# ir_remote_v2.net
KiCad netlist of a schematic drawn in EAGLE
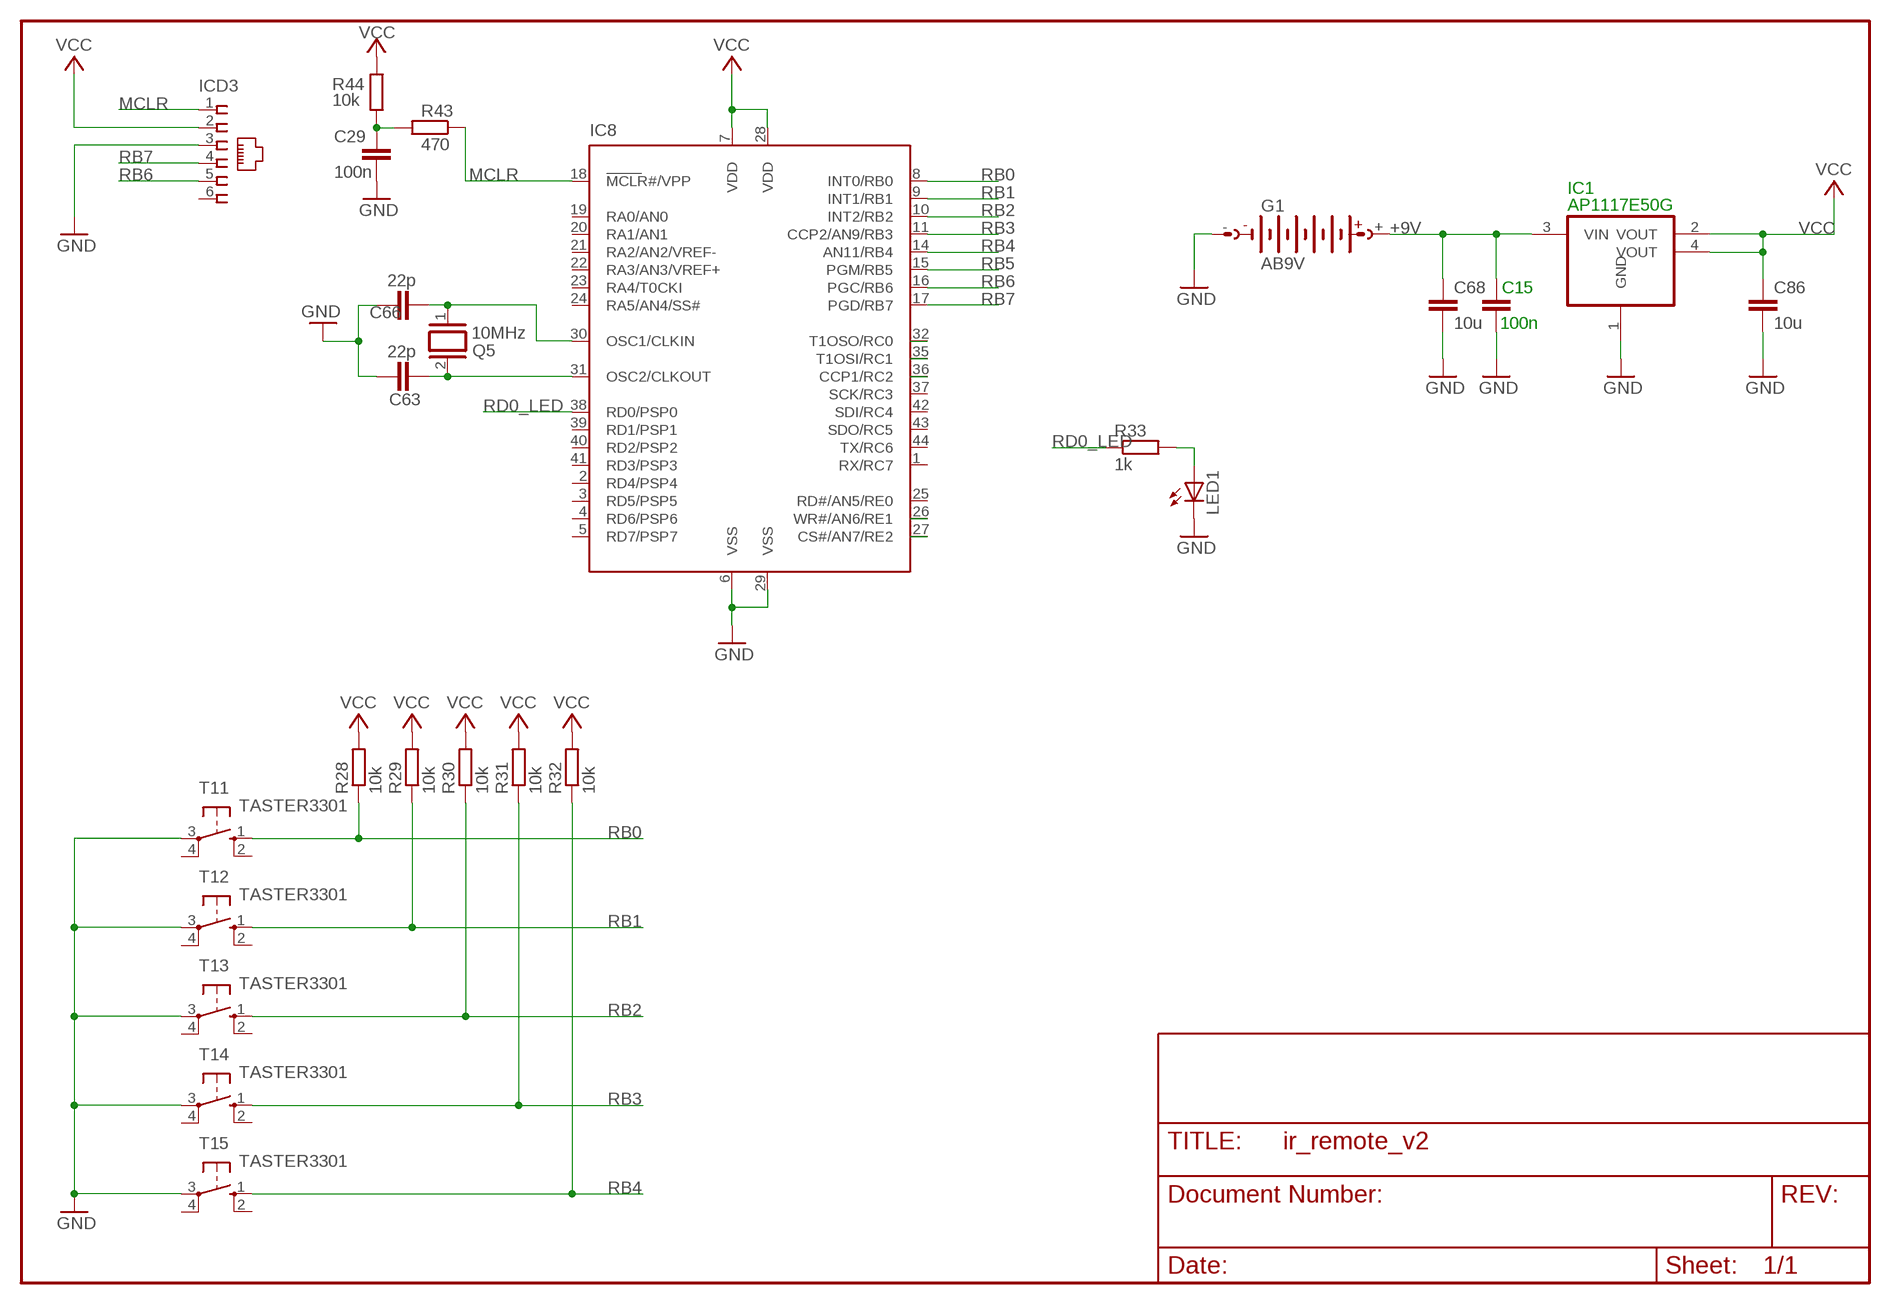
[diagram p0: schematic, sheet 1]

(export (version "E")
  (design (tool "Eeschema 10.0.6"))
  (components
    (comp (ref "C15")
      (value "100n")
      (footprint "eagle-import:C0805")
      (libsource (lib "eagle-import") (part "rcl_416_C-EUC0805"))
    )
    (comp (ref "C29")
      (value "100n")
      (footprint "eagle-import:C0805")
      (libsource (lib "eagle-import") (part "C-EUC0805"))
    )
    (comp (ref "C63")
      (value "22p")
      (footprint "eagle-import:C0603_WE")
      (libsource (lib "eagle-import") (part "C-EUC0603_WE"))
    )
    (comp (ref "C66")
      (value "22p")
      (footprint "eagle-import:C0603_WE")
      (libsource (lib "eagle-import") (part "C-EUC0603_WE"))
    )
    (comp (ref "C68")
      (value "10u")
      (footprint "eagle-import:C0805")
      (libsource (lib "eagle-import") (part "C-EUC0805"))
    )
    (comp (ref "C86")
      (value "10u")
      (footprint "eagle-import:C0805")
      (libsource (lib "eagle-import") (part "C-EUC0805"))
    )
    (comp (ref "G1")
      (value "AB9V")
      (footprint "eagle-import:AB9V")
      (libsource (lib "eagle-import") (part "AB9V"))
    )
    (comp (ref "IC1")
      (value "AP1117E50G")
      (footprint "eagle-import:SOT223")
      (libsource (lib "eagle-import") (part "REG1117-2OUT"))
    )
    (comp (ref "IC8")
      (value "PIC18F4520")
      (footprint "eagle-import:TQFP44")
      (libsource (lib "eagle-import") (part "PIC18F4520"))
    )
    (comp (ref "ICD3")
      (value "520250-3")
      (footprint "eagle-import:520250-3")
      (libsource (lib "eagle-import") (part "520250-3"))
    )
    (comp (ref "LED1")
      (value "LED5MM")
      (footprint "eagle-import:LED5MM")
      (libsource (lib "eagle-import") (part "LED5MM"))
    )
    (comp (ref "Q5")
      (value "10MHz")
      (footprint "eagle-import:QUARZ_HC5032_2")
      (libsource (lib "eagle-import") (part "XTAL_HC5032"))
    )
    (comp (ref "R28")
      (value "10k")
      (footprint "eagle-import:0207_7")
      (libsource (lib "eagle-import") (part "R-EU_0207/7"))
    )
    (comp (ref "R29")
      (value "10k")
      (footprint "eagle-import:0207_7")
      (libsource (lib "eagle-import") (part "R-EU_0207/7"))
    )
    (comp (ref "R30")
      (value "10k")
      (footprint "eagle-import:0207_7")
      (libsource (lib "eagle-import") (part "R-EU_0207/7"))
    )
    (comp (ref "R31")
      (value "10k")
      (footprint "eagle-import:0207_7")
      (libsource (lib "eagle-import") (part "R-EU_0207/7"))
    )
    (comp (ref "R32")
      (value "10k")
      (footprint "eagle-import:0207_7")
      (libsource (lib "eagle-import") (part "R-EU_0207/7"))
    )
    (comp (ref "R33")
      (value "1k")
      (footprint "eagle-import:0207_10")
      (libsource (lib "eagle-import") (part "resistor_R-EU_0207/10"))
    )
    (comp (ref "R43")
      (value "470")
      (footprint "eagle-import:M0805")
      (libsource (lib "eagle-import") (part "R-EU_M0805"))
    )
    (comp (ref "R44")
      (value "10k")
      (footprint "eagle-import:M0805")
      (libsource (lib "eagle-import") (part "R-EU_M0805"))
    )
    (comp (ref "T11")
      (value "TASTER3301")
      (footprint "eagle-import:TASTER3301")
      (libsource (lib "eagle-import") (part "TASTER3301"))
    )
    (comp (ref "T12")
      (value "TASTER3301")
      (footprint "eagle-import:TASTER3301")
      (libsource (lib "eagle-import") (part "TASTER3301"))
    )
    (comp (ref "T13")
      (value "TASTER3301")
      (footprint "eagle-import:TASTER3301")
      (libsource (lib "eagle-import") (part "TASTER3301"))
    )
    (comp (ref "T14")
      (value "TASTER3301")
      (footprint "eagle-import:TASTER3301")
      (libsource (lib "eagle-import") (part "TASTER3301"))
    )
    (comp (ref "T15")
      (value "TASTER3301")
      (footprint "eagle-import:TASTER3301")
      (libsource (lib "eagle-import") (part "TASTER3301"))
    )
  )
  (nets
    (net (code "1") (name "/+9V") (class "Default")
      (node (ref "C15") (pin "1") (pinfunction "1_1") (pintype "passive"))
      (node (ref "C68") (pin "1") (pinfunction "1_1") (pintype "passive"))
      (node (ref "G1") (pin "+") (pinfunction "+_+") (pintype "passive"))
      (node (ref "IC1") (pin "3") (pinfunction "VIN_3") (pintype "input"))
    )
    (net (code "2") (name "/MCLR") (class "Default")
      (node (ref "IC8") (pin "18") (pinfunction "MCLR#/VPP_18") (pintype "input"))
      (node (ref "ICD3") (pin "1") (pinfunction "1_1") (pintype "passive"))
      (node (ref "R43") (pin "1") (pinfunction "1_1") (pintype "passive"))
    )
    (net (code "3") (name "/RB0") (class "Default")
      (node (ref "IC8") (pin "8") (pinfunction "INT0/RB0_8") (pintype "bidirectional"))
      (node (ref "R28") (pin "1") (pinfunction "1_1") (pintype "passive"))
      (node (ref "T11") (pin "1") (pinfunction "S_1") (pintype "passive"))
    )
    (net (code "4") (name "/RB1") (class "Default")
      (node (ref "IC8") (pin "35") (pinfunction "T1OSI/RC1_35") (pintype "bidirectional"))
      (node (ref "IC8") (pin "9") (pinfunction "INT1/RB1_9") (pintype "bidirectional"))
      (node (ref "R29") (pin "1") (pinfunction "1_1") (pintype "passive"))
      (node (ref "T12") (pin "1") (pinfunction "S_1") (pintype "passive"))
    )
    (net (code "5") (name "/RB2") (class "Default")
      (node (ref "IC8") (pin "10") (pinfunction "INT2/RB2_10") (pintype "bidirectional"))
      (node (ref "IC8") (pin "32") (pinfunction "T1OSO/RC0_32") (pintype "bidirectional"))
      (node (ref "R30") (pin "1") (pinfunction "1_1") (pintype "passive"))
      (node (ref "T13") (pin "1") (pinfunction "S_1") (pintype "passive"))
    )
    (net (code "6") (name "/RB3") (class "Default")
      (node (ref "IC8") (pin "11") (pinfunction "CCP2/AN9/RB3_11") (pintype "bidirectional"))
      (node (ref "R31") (pin "1") (pinfunction "1_1") (pintype "passive"))
      (node (ref "T14") (pin "1") (pinfunction "S_1") (pintype "passive"))
    )
    (net (code "7") (name "/RB4") (class "Default")
      (node (ref "IC8") (pin "14") (pinfunction "AN11/RB4_14") (pintype "bidirectional"))
      (node (ref "R32") (pin "1") (pinfunction "1_1") (pintype "passive"))
      (node (ref "T15") (pin "1") (pinfunction "S_1") (pintype "passive"))
    )
    (net (code "8") (name "/RB5") (class "Default")
      (node (ref "IC8") (pin "15") (pinfunction "PGM/RB5_15") (pintype "bidirectional"))
    )
    (net (code "9") (name "/RB6") (class "Default")
      (node (ref "IC8") (pin "16") (pinfunction "PGC/RB6_16") (pintype "bidirectional"))
      (node (ref "ICD3") (pin "5") (pinfunction "5_5") (pintype "passive"))
    )
    (net (code "10") (name "/RB7") (class "Default")
      (node (ref "IC8") (pin "17") (pinfunction "PGD/RB7_17") (pintype "bidirectional"))
      (node (ref "ICD3") (pin "4") (pinfunction "4_4") (pintype "passive"))
    )
    (net (code "11") (name "/RD0_LED") (class "Default")
      (node (ref "IC8") (pin "38") (pinfunction "RD0/PSP0_38") (pintype "bidirectional"))
      (node (ref "R33") (pin "1") (pinfunction "1_1") (pintype "passive"))
    )
    (net (code "12") (name "GND") (class "Default")
      (node (ref "C15") (pin "2") (pinfunction "2_2") (pintype "passive"))
      (node (ref "C29") (pin "2") (pinfunction "2_2") (pintype "passive"))
      (node (ref "C63") (pin "1") (pinfunction "1_1") (pintype "passive"))
      (node (ref "C66") (pin "1") (pinfunction "1_1") (pintype "passive"))
      (node (ref "C68") (pin "2") (pinfunction "2_2") (pintype "passive"))
      (node (ref "C86") (pin "2") (pinfunction "2_2") (pintype "passive"))
      (node (ref "G1") (pin "-") (pinfunction "-_-") (pintype "passive"))
      (node (ref "IC1") (pin "1") (pinfunction "GND_1") (pintype "power_in"))
      (node (ref "IC8") (pin "29") (pinfunction "VSS_29") (pintype "bidirectional"))
      (node (ref "IC8") (pin "6") (pinfunction "VSS_6") (pintype "bidirectional"))
      (node (ref "ICD3") (pin "3") (pinfunction "3_3") (pintype "passive"))
      (node (ref "LED1") (pin "K") (pinfunction "C_K") (pintype "passive"))
      (node (ref "T11") (pin "3") (pinfunction "P_3") (pintype "passive"))
      (node (ref "T12") (pin "3") (pinfunction "P_3") (pintype "passive"))
      (node (ref "T13") (pin "3") (pinfunction "P_3") (pintype "passive"))
      (node (ref "T14") (pin "3") (pinfunction "P_3") (pintype "passive"))
      (node (ref "T15") (pin "3") (pinfunction "P_3") (pintype "passive"))
    )
    (net (code "13") (name "Net-(C29-Pad1)") (class "Default")
      (node (ref "C29") (pin "1") (pinfunction "1_1") (pintype "passive"))
      (node (ref "R43") (pin "2") (pinfunction "2_2") (pintype "passive"))
      (node (ref "R44") (pin "2") (pinfunction "2_2") (pintype "passive"))
    )
    (net (code "14") (name "Net-(IC8-OSC1{slash}CLKIN)") (class "Default")
      (node (ref "C66") (pin "2") (pinfunction "2_2") (pintype "passive"))
      (node (ref "IC8") (pin "30") (pinfunction "OSC1/CLKIN_30") (pintype "input"))
      (node (ref "Q5") (pin "1") (pinfunction "1_1") (pintype "passive"))
    )
    (net (code "15") (name "Net-(IC8-OSC2{slash}CLKOUT)") (class "Default")
      (node (ref "C63") (pin "2") (pinfunction "2_2") (pintype "passive"))
      (node (ref "IC8") (pin "31") (pinfunction "OSC2/CLKOUT_31") (pintype "output"))
      (node (ref "Q5") (pin "2") (pinfunction "2_2") (pintype "passive"))
    )
    (net (code "16") (name "Net-(LED1-PadA)") (class "Default")
      (node (ref "LED1") (pin "A") (pinfunction "A_A") (pintype "passive"))
      (node (ref "R33") (pin "2") (pinfunction "2_2") (pintype "passive"))
    )
    (net (code "17") (name "VCC") (class "Default")
      (node (ref "C86") (pin "1") (pinfunction "1_1") (pintype "passive"))
      (node (ref "IC1") (pin "2") (pinfunction "VOUT_2") (pintype "output"))
      (node (ref "IC1") (pin "4") (pinfunction "VOUT_4") (pintype "bidirectional"))
      (node (ref "IC8") (pin "28") (pinfunction "VDD_28") (pintype "bidirectional"))
      (node (ref "IC8") (pin "7") (pinfunction "VDD_7") (pintype "bidirectional"))
      (node (ref "ICD3") (pin "2") (pinfunction "2_2") (pintype "passive"))
      (node (ref "R28") (pin "2") (pinfunction "2_2") (pintype "passive"))
      (node (ref "R29") (pin "2") (pinfunction "2_2") (pintype "passive"))
      (node (ref "R30") (pin "2") (pinfunction "2_2") (pintype "passive"))
      (node (ref "R31") (pin "2") (pinfunction "2_2") (pintype "passive"))
      (node (ref "R32") (pin "2") (pinfunction "2_2") (pintype "passive"))
      (node (ref "R44") (pin "1") (pinfunction "1_1") (pintype "passive"))
    )
    (net (code "18") (name "unconnected-(IC8-CCP1{slash}RC2-Pad36)") (class "Default")
      (node (ref "IC8") (pin "36") (pinfunction "CCP1/RC2_36") (pintype "bidirectional"))
    )
    (net (code "19") (name "unconnected-(IC8-CS#{slash}AN7{slash}RE2-Pad27)") (class "Default")
      (node (ref "IC8") (pin "27") (pinfunction "CS#/AN7/RE2_27") (pintype "bidirectional"))
    )
    (net (code "20") (name "unconnected-(IC8-RA0{slash}AN0-Pad19)") (class "Default")
      (node (ref "IC8") (pin "19") (pinfunction "RA0/AN0_19") (pintype "bidirectional"))
    )
    (net (code "21") (name "unconnected-(IC8-RA1{slash}AN1-Pad20)") (class "Default")
      (node (ref "IC8") (pin "20") (pinfunction "RA1/AN1_20") (pintype "bidirectional"))
    )
    (net (code "22") (name "unconnected-(IC8-RA2{slash}AN2{slash}VREF--Pad21)") (class "Default")
      (node (ref "IC8") (pin "21") (pinfunction "RA2/AN2/VREF-_21") (pintype "bidirectional"))
    )
    (net (code "23") (name "unconnected-(IC8-RA3{slash}AN3{slash}VREF+-Pad22)") (class "Default")
      (node (ref "IC8") (pin "22") (pinfunction "RA3/AN3/VREF+_22") (pintype "bidirectional"))
    )
    (net (code "24") (name "unconnected-(IC8-RA4{slash}T0CKI-Pad23)") (class "Default")
      (node (ref "IC8") (pin "23") (pinfunction "RA4/T0CKI_23") (pintype "bidirectional"))
    )
    (net (code "25") (name "unconnected-(IC8-RA5{slash}AN4{slash}SS#-Pad24)") (class "Default")
      (node (ref "IC8") (pin "24") (pinfunction "RA5/AN4/SS#_24") (pintype "bidirectional"))
    )
    (net (code "26") (name "unconnected-(IC8-RD#{slash}AN5{slash}RE0-Pad25)") (class "Default")
      (node (ref "IC8") (pin "25") (pinfunction "RD#/AN5/RE0_25") (pintype "bidirectional"))
    )
    (net (code "27") (name "unconnected-(IC8-RD1{slash}PSP1-Pad39)") (class "Default")
      (node (ref "IC8") (pin "39") (pinfunction "RD1/PSP1_39") (pintype "bidirectional"))
    )
    (net (code "28") (name "unconnected-(IC8-RD2{slash}PSP2-Pad40)") (class "Default")
      (node (ref "IC8") (pin "40") (pinfunction "RD2/PSP2_40") (pintype "bidirectional"))
    )
    (net (code "29") (name "unconnected-(IC8-RD3{slash}PSP3-Pad41)") (class "Default")
      (node (ref "IC8") (pin "41") (pinfunction "RD3/PSP3_41") (pintype "bidirectional"))
    )
    (net (code "30") (name "unconnected-(IC8-RD4{slash}PSP4-Pad2)") (class "Default")
      (node (ref "IC8") (pin "2") (pinfunction "RD4/PSP4_2") (pintype "bidirectional"))
    )
    (net (code "31") (name "unconnected-(IC8-RD5{slash}PSP5-Pad3)") (class "Default")
      (node (ref "IC8") (pin "3") (pinfunction "RD5/PSP5_3") (pintype "bidirectional"))
    )
    (net (code "32") (name "unconnected-(IC8-RD6{slash}PSP6-Pad4)") (class "Default")
      (node (ref "IC8") (pin "4") (pinfunction "RD6/PSP6_4") (pintype "bidirectional"))
    )
    (net (code "33") (name "unconnected-(IC8-RD7{slash}PSP7-Pad5)") (class "Default")
      (node (ref "IC8") (pin "5") (pinfunction "RD7/PSP7_5") (pintype "bidirectional"))
    )
    (net (code "34") (name "unconnected-(IC8-RX{slash}RC7-Pad1)") (class "Default")
      (node (ref "IC8") (pin "1") (pinfunction "RX/RC7_1") (pintype "bidirectional"))
    )
    (net (code "35") (name "unconnected-(IC8-SCK{slash}RC3-Pad37)") (class "Default")
      (node (ref "IC8") (pin "37") (pinfunction "SCK/RC3_37") (pintype "bidirectional"))
    )
    (net (code "36") (name "unconnected-(IC8-SDI{slash}RC4-Pad42)") (class "Default")
      (node (ref "IC8") (pin "42") (pinfunction "SDI/RC4_42") (pintype "bidirectional"))
    )
    (net (code "37") (name "unconnected-(IC8-SDO{slash}RC5-Pad43)") (class "Default")
      (node (ref "IC8") (pin "43") (pinfunction "SDO/RC5_43") (pintype "bidirectional"))
    )
    (net (code "38") (name "unconnected-(IC8-TX{slash}RC6-Pad44)") (class "Default")
      (node (ref "IC8") (pin "44") (pinfunction "TX/RC6_44") (pintype "bidirectional"))
    )
    (net (code "39") (name "unconnected-(IC8-WR#{slash}AN6{slash}RE1-Pad26)") (class "Default")
      (node (ref "IC8") (pin "26") (pinfunction "WR#/AN6/RE1_26") (pintype "bidirectional"))
    )
    (net (code "40") (name "unconnected-(ICD3-Pad6)") (class "Default")
      (node (ref "ICD3") (pin "6") (pinfunction "6_6") (pintype "passive"))
    )
    (net (code "41") (name "unconnected-(T11-P1-Pad4)") (class "Default")
      (node (ref "T11") (pin "4") (pinfunction "P1_4") (pintype "passive"))
    )
    (net (code "42") (name "unconnected-(T11-S1-Pad2)") (class "Default")
      (node (ref "T11") (pin "2") (pinfunction "S1_2") (pintype "passive"))
    )
    (net (code "43") (name "unconnected-(T12-P1-Pad4)") (class "Default")
      (node (ref "T12") (pin "4") (pinfunction "P1_4") (pintype "passive"))
    )
    (net (code "44") (name "unconnected-(T12-S1-Pad2)") (class "Default")
      (node (ref "T12") (pin "2") (pinfunction "S1_2") (pintype "passive"))
    )
    (net (code "45") (name "unconnected-(T13-P1-Pad4)") (class "Default")
      (node (ref "T13") (pin "4") (pinfunction "P1_4") (pintype "passive"))
    )
    (net (code "46") (name "unconnected-(T13-S1-Pad2)") (class "Default")
      (node (ref "T13") (pin "2") (pinfunction "S1_2") (pintype "passive"))
    )
    (net (code "47") (name "unconnected-(T14-P1-Pad4)") (class "Default")
      (node (ref "T14") (pin "4") (pinfunction "P1_4") (pintype "passive"))
    )
    (net (code "48") (name "unconnected-(T14-S1-Pad2)") (class "Default")
      (node (ref "T14") (pin "2") (pinfunction "S1_2") (pintype "passive"))
    )
    (net (code "49") (name "unconnected-(T15-P1-Pad4)") (class "Default")
      (node (ref "T15") (pin "4") (pinfunction "P1_4") (pintype "passive"))
    )
    (net (code "50") (name "unconnected-(T15-S1-Pad2)") (class "Default")
      (node (ref "T15") (pin "2") (pinfunction "S1_2") (pintype "passive"))
    )
  )
)
